# Servo8.net
KiCad netlist of a schematic drawn in EAGLE
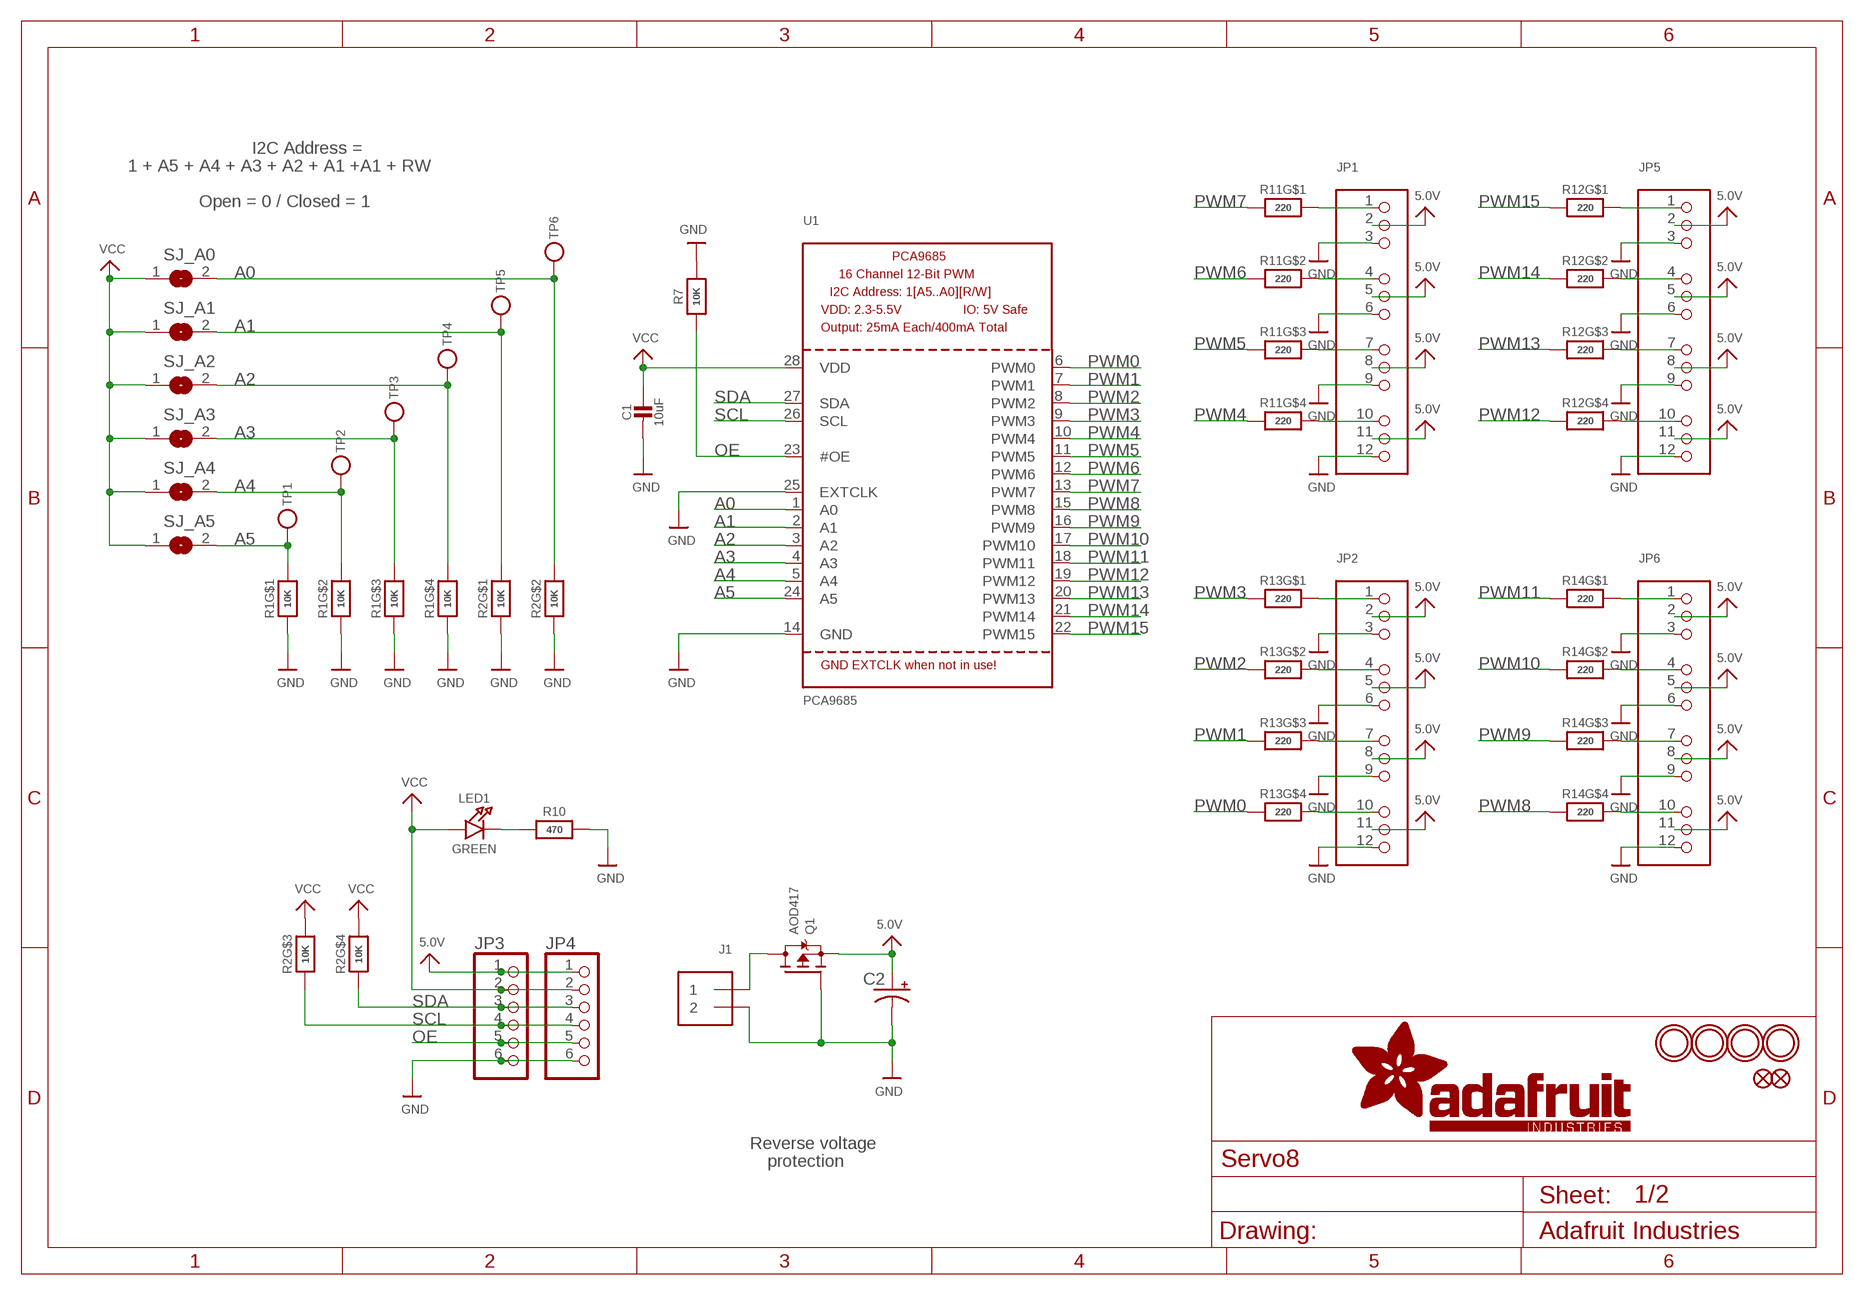
[diagram p0: schematic, sheet 1]
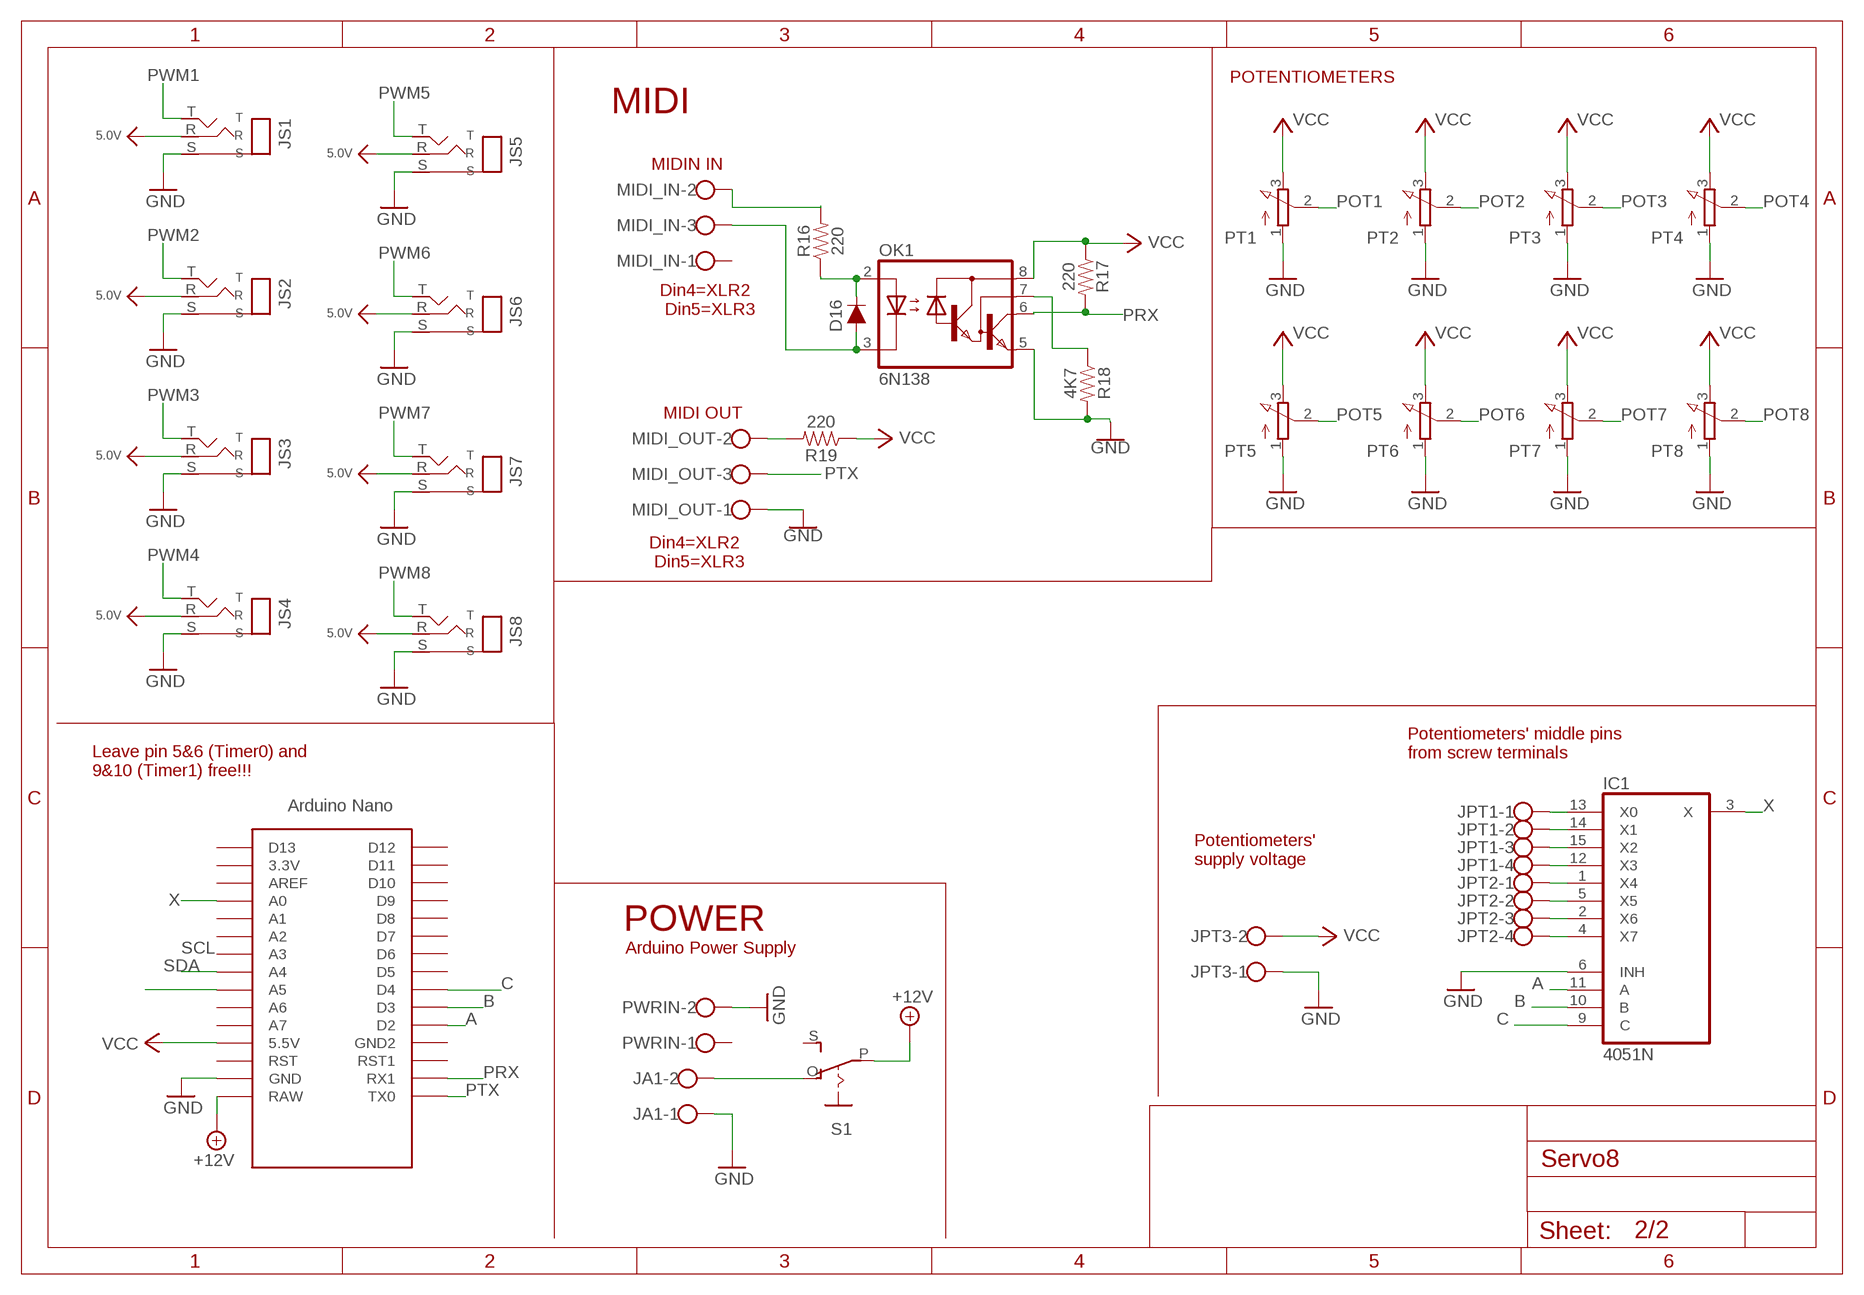
[diagram p1: schematic, sheet 2]

(export (version "E")
  (design (tool "Eeschema 10.0.6"))
  (components
    (comp (ref "C1")
      (value "10uF")
      (footprint "eagle-import:0805-NO")
      (libsource (lib "eagle-import") (part "CAP_CERAMIC0805-NOOUTLINE"))
    )
    (comp (ref "C2")
      (value "CPOL-USE3.5-8")
      (footprint "eagle-import:E3,5-8")
      (libsource (lib "eagle-import") (part "CPOL-USE3.5-8"))
    )
    (comp (ref "FID1")
      (value "FIDUCIAL\"\"")
      (footprint "eagle-import:FIDUCIAL_1MM")
      (libsource (lib "eagle-import") (part "FIDUCIAL{dblquote}{dblquote}"))
    )
    (comp (ref "FID2")
      (value "FIDUCIAL\"\"")
      (footprint "eagle-import:FIDUCIAL_1MM")
      (libsource (lib "eagle-import") (part "FIDUCIAL{dblquote}{dblquote}"))
    )
    (comp (ref "J1")
      (value "TERMBLOCK_1X2")
      (footprint "eagle-import:TERMBLOCK_1X2-3.5MM")
      (libsource (lib "eagle-import") (part "TERMBLOCK_1X2"))
    )
    (comp (ref "JP1")
      (value "HEADER-3X04")
      (footprint "eagle-import:3X04")
      (libsource (lib "eagle-import") (part "HEADER-3X04"))
    )
    (comp (ref "JP2")
      (value "HEADER-3X04")
      (footprint "eagle-import:3X04")
      (libsource (lib "eagle-import") (part "HEADER-3X04"))
    )
    (comp (ref "JP3")
      (value "PINHD-1X6CB")
      (footprint "eagle-import:1X06-CLEANBIG")
      (libsource (lib "eagle-import") (part "PINHD-1X6CB"))
    )
    (comp (ref "JP4")
      (value "PINHD-1X6CB")
      (footprint "eagle-import:1X06-CLEANBIG")
      (libsource (lib "eagle-import") (part "PINHD-1X6CB"))
    )
    (comp (ref "JP5")
      (value "HEADER-3X04")
      (footprint "eagle-import:3X04")
      (libsource (lib "eagle-import") (part "HEADER-3X04"))
    )
    (comp (ref "JP6")
      (value "HEADER-3X04")
      (footprint "eagle-import:3X04")
      (libsource (lib "eagle-import") (part "HEADER-3X04"))
    )
    (comp (ref "LED1")
      (value "GREEN")
      (footprint "eagle-import:CHIPLED_0805_NOOUTLINE")
      (libsource (lib "eagle-import") (part "LED0805_NOOUTLINE"))
    )
    (comp (ref "Q1")
      (value "AOD417")
      (footprint "eagle-import:TO252")
      (libsource (lib "eagle-import") (part "MOSFET-PTO252"))
    )
    (comp (ref "R1")
      (value "10K")
      (footprint "eagle-import:RESPACK_4X0603")
      (libsource (lib "eagle-import") (part "RESISTOR_4PACK"))
    )
    (comp (ref "R2")
      (value "10K")
      (footprint "eagle-import:RESPACK_4X0603")
      (libsource (lib "eagle-import") (part "RESISTOR_4PACK"))
    )
    (comp (ref "R7")
      (value "10K")
      (footprint "eagle-import:0805-NO")
      (libsource (lib "eagle-import") (part "RESISTOR0805_NOOUTLINE"))
    )
    (comp (ref "R10")
      (value "470")
      (footprint "eagle-import:_0805MP")
      (libsource (lib "eagle-import") (part "RESISTOR_0805MP"))
    )
    (comp (ref "R11")
      (value "220")
      (footprint "eagle-import:RESPACK_4X0603")
      (libsource (lib "eagle-import") (part "RESISTOR_4PACK"))
    )
    (comp (ref "R12")
      (value "220")
      (footprint "eagle-import:RESPACK_4X0603")
      (libsource (lib "eagle-import") (part "RESISTOR_4PACK"))
    )
    (comp (ref "R13")
      (value "220")
      (footprint "eagle-import:RESPACK_4X0603")
      (libsource (lib "eagle-import") (part "RESISTOR_4PACK"))
    )
    (comp (ref "R14")
      (value "220")
      (footprint "eagle-import:RESPACK_4X0603")
      (libsource (lib "eagle-import") (part "RESISTOR_4PACK"))
    )
    (comp (ref "SJ_A0")
      (value "SOLDERJUMPERREFLOW_NOPASTE")
      (footprint "eagle-import:SOLDERJUMPER_REFLOW_NOPASTE")
      (libsource (lib "eagle-import") (part "SOLDERJUMPERREFLOW_NOPASTE"))
    )
    (comp (ref "SJ_A1")
      (value "SOLDERJUMPERREFLOW_NOPASTE")
      (footprint "eagle-import:SOLDERJUMPER_REFLOW_NOPASTE")
      (libsource (lib "eagle-import") (part "SOLDERJUMPERREFLOW_NOPASTE"))
    )
    (comp (ref "SJ_A2")
      (value "SOLDERJUMPERREFLOW_NOPASTE")
      (footprint "eagle-import:SOLDERJUMPER_REFLOW_NOPASTE")
      (libsource (lib "eagle-import") (part "SOLDERJUMPERREFLOW_NOPASTE"))
    )
    (comp (ref "SJ_A3")
      (value "SOLDERJUMPERREFLOW_NOPASTE")
      (footprint "eagle-import:SOLDERJUMPER_REFLOW_NOPASTE")
      (libsource (lib "eagle-import") (part "SOLDERJUMPERREFLOW_NOPASTE"))
    )
    (comp (ref "SJ_A4")
      (value "SOLDERJUMPERREFLOW_NOPASTE")
      (footprint "eagle-import:SOLDERJUMPER_REFLOW_NOPASTE")
      (libsource (lib "eagle-import") (part "SOLDERJUMPERREFLOW_NOPASTE"))
    )
    (comp (ref "SJ_A5")
      (value "SOLDERJUMPERREFLOW_NOPASTE")
      (footprint "eagle-import:SOLDERJUMPER_REFLOW_NOPASTE")
      (libsource (lib "eagle-import") (part "SOLDERJUMPERREFLOW_NOPASTE"))
    )
    (comp (ref "TP1")
      (value "TESTPOINTROUND1MM")
      (footprint "eagle-import:TESTPOINT_ROUND_1MM")
      (libsource (lib "eagle-import") (part "TESTPOINTROUND1MM"))
    )
    (comp (ref "TP2")
      (value "TESTPOINTROUND1MM")
      (footprint "eagle-import:TESTPOINT_ROUND_1MM")
      (libsource (lib "eagle-import") (part "TESTPOINTROUND1MM"))
    )
    (comp (ref "TP3")
      (value "TESTPOINTROUND1MM")
      (footprint "eagle-import:TESTPOINT_ROUND_1MM")
      (libsource (lib "eagle-import") (part "TESTPOINTROUND1MM"))
    )
    (comp (ref "TP4")
      (value "TESTPOINTROUND1MM")
      (footprint "eagle-import:TESTPOINT_ROUND_1MM")
      (libsource (lib "eagle-import") (part "TESTPOINTROUND1MM"))
    )
    (comp (ref "TP5")
      (value "TESTPOINTROUND1MM")
      (footprint "eagle-import:TESTPOINT_ROUND_1MM")
      (libsource (lib "eagle-import") (part "TESTPOINTROUND1MM"))
    )
    (comp (ref "TP6")
      (value "TESTPOINTROUND1MM")
      (footprint "eagle-import:TESTPOINT_ROUND_1MM")
      (libsource (lib "eagle-import") (part "TESTPOINTROUND1MM"))
    )
    (comp (ref "U$47")
      (value "MOUNTINGHOLE2.5")
      (footprint "eagle-import:MOUNTINGHOLE_2.5_PLATED")
      (libsource (lib "eagle-import") (part "MOUNTINGHOLE2.5"))
    )
    (comp (ref "U$48")
      (value "MOUNTINGHOLE2.5")
      (footprint "eagle-import:MOUNTINGHOLE_2.5_PLATED")
      (libsource (lib "eagle-import") (part "MOUNTINGHOLE2.5"))
    )
    (comp (ref "U$49")
      (value "MOUNTINGHOLE2.5")
      (footprint "eagle-import:MOUNTINGHOLE_2.5_PLATED")
      (libsource (lib "eagle-import") (part "MOUNTINGHOLE2.5"))
    )
    (comp (ref "U$50")
      (value "MOUNTINGHOLE2.5")
      (footprint "eagle-import:MOUNTINGHOLE_2.5_PLATED")
      (libsource (lib "eagle-import") (part "MOUNTINGHOLE2.5"))
    )
    (comp (ref "U1")
      (value "PCA9685")
      (footprint "eagle-import:TSSOP28")
      (libsource (lib "eagle-import") (part "PCA9685"))
    )
    (comp (ref "D16")
      (value "200mA/100V/1V")
      (footprint "eagle-import:DIODE-1N4148")
      (libsource (lib "eagle-import") (part "DIODE-1N4148"))
    )
    (comp (ref "IC1")
      (value "4051N")
      (footprint "eagle-import:DIL16")
      (libsource (lib "eagle-import") (part "4051N"))
    )
    (comp (ref "JA1")
      (value "W237-102")
      (footprint "eagle-import:W237-102")
      (fields (field (name "MPN") "237-102"))
      (libsource (lib "eagle-import") (part "W237-102"))
    )
    (comp (ref "JPT1")
      (value "W237-4")
      (footprint "eagle-import:W237-4")
      (libsource (lib "eagle-import") (part "W237-4"))
    )
    (comp (ref "JPT2")
      (value "W237-4")
      (footprint "eagle-import:W237-4")
      (libsource (lib "eagle-import") (part "W237-4"))
    )
    (comp (ref "JPT3")
      (value "W237-102")
      (footprint "eagle-import:W237-102")
      (fields (field (name "MPN") "237-102"))
      (libsource (lib "eagle-import") (part "W237-102"))
    )
    (comp (ref "JS1")
      (value "STEREOREV")
      (footprint "eagle-import:STEREO_JACK_MIRROR")
      (libsource (lib "eagle-import") (part "STEREOREV"))
    )
    (comp (ref "JS2")
      (value "STEREOREV")
      (footprint "eagle-import:STEREO_JACK_MIRROR")
      (libsource (lib "eagle-import") (part "STEREOREV"))
    )
    (comp (ref "JS3")
      (value "STEREOREV")
      (footprint "eagle-import:STEREO_JACK_MIRROR")
      (libsource (lib "eagle-import") (part "STEREOREV"))
    )
    (comp (ref "JS4")
      (value "STEREOREV")
      (footprint "eagle-import:STEREO_JACK_MIRROR")
      (libsource (lib "eagle-import") (part "STEREOREV"))
    )
    (comp (ref "JS5")
      (value "STEREOREV")
      (footprint "eagle-import:STEREO_JACK_MIRROR")
      (libsource (lib "eagle-import") (part "STEREOREV"))
    )
    (comp (ref "JS6")
      (value "STEREOREV")
      (footprint "eagle-import:STEREO_JACK_MIRROR")
      (libsource (lib "eagle-import") (part "STEREOREV"))
    )
    (comp (ref "JS7")
      (value "STEREOREV")
      (footprint "eagle-import:STEREO_JACK_MIRROR")
      (libsource (lib "eagle-import") (part "STEREOREV"))
    )
    (comp (ref "JS8")
      (value "STEREOREV")
      (footprint "eagle-import:STEREO_JACK_MIRROR")
      (libsource (lib "eagle-import") (part "STEREOREV"))
    )
    (comp (ref "MIDI_IN")
      (value "W237-103")
      (footprint "eagle-import:W237-103")
      (fields (field (name "MPN") "237-103"))
      (libsource (lib "eagle-import") (part "W237-103"))
    )
    (comp (ref "MIDI_OUT")
      (value "W237-103")
      (footprint "eagle-import:W237-103")
      (fields (field (name "MPN") "237-103"))
      (libsource (lib "eagle-import") (part "W237-103"))
    )
    (comp (ref "OK1")
      (value "6N138")
      (footprint "eagle-import:DIL08")
      (fields (field (name "MF") "VISHAY/TELEFUNKEN"))
      (libsource (lib "eagle-import") (part "6N138"))
    )
    (comp (ref "PT1")
      (value "3RP/1610N")
      (footprint "eagle-import:3RP_1610N")
      (libsource (lib "eagle-import") (part "3RP/1610N"))
    )
    (comp (ref "PT2")
      (value "3RP/1610N")
      (footprint "eagle-import:3RP_1610N")
      (libsource (lib "eagle-import") (part "3RP/1610N"))
    )
    (comp (ref "PT3")
      (value "3RP/1610N")
      (footprint "eagle-import:3RP_1610N")
      (libsource (lib "eagle-import") (part "3RP/1610N"))
    )
    (comp (ref "PT4")
      (value "3RP/1610N")
      (footprint "eagle-import:3RP_1610N")
      (libsource (lib "eagle-import") (part "3RP/1610N"))
    )
    (comp (ref "PT5")
      (value "3RP/1610N")
      (footprint "eagle-import:3RP_1610N")
      (libsource (lib "eagle-import") (part "3RP/1610N"))
    )
    (comp (ref "PT6")
      (value "3RP/1610N")
      (footprint "eagle-import:3RP_1610N")
      (libsource (lib "eagle-import") (part "3RP/1610N"))
    )
    (comp (ref "PT7")
      (value "3RP/1610N")
      (footprint "eagle-import:3RP_1610N")
      (libsource (lib "eagle-import") (part "3RP/1610N"))
    )
    (comp (ref "PT8")
      (value "3RP/1610N")
      (footprint "eagle-import:3RP_1610N")
      (libsource (lib "eagle-import") (part "3RP/1610N"))
    )
    (comp (ref "PWRIN")
      (value "W237-4")
      (footprint "eagle-import:W237-4")
      (libsource (lib "eagle-import") (part "W237-4"))
    )
    (comp (ref "R16")
      (value "220")
      (footprint "eagle-import:AXIAL-0.3")
      (libsource (lib "eagle-import") (part "1KOHM-HORIZ-1/4W-5%"))
    )
    (comp (ref "R17")
      (value "220")
      (footprint "eagle-import:AXIAL-0.3")
      (libsource (lib "eagle-import") (part "1KOHM-HORIZ-1/4W-5%"))
    )
    (comp (ref "R18")
      (value "4K7")
      (footprint "eagle-import:AXIAL-0.3")
      (libsource (lib "eagle-import") (part "1KOHM-HORIZ-1/4W-5%"))
    )
    (comp (ref "R19")
      (value "220")
      (footprint "eagle-import:AXIAL-0.3")
      (libsource (lib "eagle-import") (part "1KOHM-HORIZ-1/4W-5%"))
    )
    (comp (ref "S1")
      (value "EG1218S")
      (footprint "eagle-import:EG1218")
      (libsource (lib "eagle-import") (part "EG1218S"))
    )
    (comp (ref "U$55")
      (value "NANO")
      (footprint "eagle-import:NANO")
      (libsource (lib "eagle-import") (part "NANO"))
    )
  )
  (nets
    (net (code "1") (name "+12V") (class "Default")
      (node (ref "S1") (pin "P") (pinfunction "P_P") (pintype "passive"))
      (node (ref "U$55") (pin "RAW") (pinfunction "RAW_RAW") (pintype "bidirectional"))
    )
    (net (code "2") (name "5.0V") (class "Default")
      (node (ref "C2") (pin "+") (pinfunction "+_+") (pintype "passive"))
      (node (ref "JP1") (pin "11") (pinfunction "11_11") (pintype "passive"))
      (node (ref "JP1") (pin "2") (pinfunction "2_2") (pintype "passive"))
      (node (ref "JP1") (pin "5") (pinfunction "5_5") (pintype "passive"))
      (node (ref "JP1") (pin "8") (pinfunction "8_8") (pintype "passive"))
      (node (ref "JP2") (pin "11") (pinfunction "11_11") (pintype "passive"))
      (node (ref "JP2") (pin "2") (pinfunction "2_2") (pintype "passive"))
      (node (ref "JP2") (pin "5") (pinfunction "5_5") (pintype "passive"))
      (node (ref "JP2") (pin "8") (pinfunction "8_8") (pintype "passive"))
      (node (ref "JP3") (pin "1") (pinfunction "1_1") (pintype "passive"))
      (node (ref "JP4") (pin "1") (pinfunction "1_1") (pintype "passive"))
      (node (ref "JP5") (pin "11") (pinfunction "11_11") (pintype "passive"))
      (node (ref "JP5") (pin "2") (pinfunction "2_2") (pintype "passive"))
      (node (ref "JP5") (pin "5") (pinfunction "5_5") (pintype "passive"))
      (node (ref "JP5") (pin "8") (pinfunction "8_8") (pintype "passive"))
      (node (ref "JP6") (pin "11") (pinfunction "11_11") (pintype "passive"))
      (node (ref "JP6") (pin "2") (pinfunction "2_2") (pintype "passive"))
      (node (ref "JP6") (pin "5") (pinfunction "5_5") (pintype "passive"))
      (node (ref "JP6") (pin "8") (pinfunction "8_8") (pintype "passive"))
      (node (ref "JS1") (pin "R") (pinfunction "R_R") (pintype "passive"))
      (node (ref "JS2") (pin "R") (pinfunction "R_R") (pintype "passive"))
      (node (ref "JS3") (pin "R") (pinfunction "R_R") (pintype "passive"))
      (node (ref "JS4") (pin "R") (pinfunction "R_R") (pintype "passive"))
      (node (ref "JS5") (pin "R") (pinfunction "R_R") (pintype "passive"))
      (node (ref "JS6") (pin "R") (pinfunction "R_R") (pintype "passive"))
      (node (ref "JS7") (pin "R") (pinfunction "R_R") (pintype "passive"))
      (node (ref "JS8") (pin "R") (pinfunction "R_R") (pintype "passive"))
      (node (ref "Q1") (pin "2") (pinfunction "S_2") (pintype "passive"))
    )
    (net (code "3") (name "A") (class "Default")
      (node (ref "IC1") (pin "11") (pinfunction "A_11") (pintype "input"))
      (node (ref "U$55") (pin "D2") (pinfunction "D2_D2") (pintype "bidirectional"))
    )
    (net (code "4") (name "A0") (class "Default")
      (node (ref "R2") (pin "7") (pinfunction "2_7") (pintype "passive"))
      (node (ref "SJ_A0") (pin "2") (pinfunction "2_2") (pintype "passive"))
      (node (ref "TP6") (pin "P$1") (pinfunction "P$1_P$1") (pintype "bidirectional"))
      (node (ref "U1") (pin "1") (pinfunction "A0_1") (pintype "bidirectional"))
    )
    (net (code "5") (name "A1") (class "Default")
      (node (ref "R2") (pin "8") (pinfunction "2_8") (pintype "passive"))
      (node (ref "SJ_A1") (pin "2") (pinfunction "2_2") (pintype "passive"))
      (node (ref "TP5") (pin "P$1") (pinfunction "P$1_P$1") (pintype "bidirectional"))
      (node (ref "U1") (pin "2") (pinfunction "A1_2") (pintype "bidirectional"))
    )
    (net (code "6") (name "A2") (class "Default")
      (node (ref "R1") (pin "5") (pinfunction "2_5") (pintype "passive"))
      (node (ref "SJ_A2") (pin "2") (pinfunction "2_2") (pintype "passive"))
      (node (ref "TP4") (pin "P$1") (pinfunction "P$1_P$1") (pintype "bidirectional"))
      (node (ref "U1") (pin "3") (pinfunction "A2_3") (pintype "bidirectional"))
    )
    (net (code "7") (name "A3") (class "Default")
      (node (ref "R1") (pin "6") (pinfunction "2_6") (pintype "passive"))
      (node (ref "SJ_A3") (pin "2") (pinfunction "2_2") (pintype "passive"))
      (node (ref "TP3") (pin "P$1") (pinfunction "P$1_P$1") (pintype "bidirectional"))
      (node (ref "U1") (pin "4") (pinfunction "A3_4") (pintype "bidirectional"))
    )
    (net (code "8") (name "A4") (class "Default")
      (node (ref "R1") (pin "7") (pinfunction "2_7") (pintype "passive"))
      (node (ref "SJ_A4") (pin "2") (pinfunction "2_2") (pintype "passive"))
      (node (ref "TP2") (pin "P$1") (pinfunction "P$1_P$1") (pintype "bidirectional"))
      (node (ref "U1") (pin "5") (pinfunction "A4_5") (pintype "bidirectional"))
    )
    (net (code "9") (name "A5") (class "Default")
      (node (ref "R1") (pin "8") (pinfunction "2_8") (pintype "passive"))
      (node (ref "SJ_A5") (pin "2") (pinfunction "2_2") (pintype "passive"))
      (node (ref "TP1") (pin "P$1") (pinfunction "P$1_P$1") (pintype "bidirectional"))
      (node (ref "U1") (pin "24") (pinfunction "A5_24") (pintype "bidirectional"))
    )
    (net (code "10") (name "B") (class "Default")
      (node (ref "IC1") (pin "10") (pinfunction "B_10") (pintype "input"))
      (node (ref "U$55") (pin "D3") (pinfunction "D3_D3") (pintype "bidirectional"))
    )
    (net (code "11") (name "C") (class "Default")
      (node (ref "IC1") (pin "9") (pinfunction "C_9") (pintype "input"))
      (node (ref "U$55") (pin "D4") (pinfunction "D4_D4") (pintype "bidirectional"))
    )
    (net (code "12") (name "GND") (class "Default")
      (node (ref "C1") (pin "2") (pinfunction "2_2") (pintype "passive"))
      (node (ref "C2") (pin "-") (pinfunction "-_-") (pintype "passive"))
      (node (ref "IC1") (pin "6") (pinfunction "INH_6") (pintype "input"))
      (node (ref "J1") (pin "2") (pinfunction "2_2") (pintype "passive"))
      (node (ref "JA1") (pin "1") (pinfunction "KL_1") (pintype "passive"))
      (node (ref "JP1") (pin "12") (pinfunction "12_12") (pintype "passive"))
      (node (ref "JP1") (pin "3") (pinfunction "3_3") (pintype "passive"))
      (node (ref "JP1") (pin "6") (pinfunction "6_6") (pintype "passive"))
      (node (ref "JP1") (pin "9") (pinfunction "9_9") (pintype "passive"))
      (node (ref "JP2") (pin "12") (pinfunction "12_12") (pintype "passive"))
      (node (ref "JP2") (pin "3") (pinfunction "3_3") (pintype "passive"))
      (node (ref "JP2") (pin "6") (pinfunction "6_6") (pintype "passive"))
      (node (ref "JP2") (pin "9") (pinfunction "9_9") (pintype "passive"))
      (node (ref "JP3") (pin "6") (pinfunction "6_6") (pintype "passive"))
      (node (ref "JP4") (pin "6") (pinfunction "6_6") (pintype "passive"))
      (node (ref "JP5") (pin "12") (pinfunction "12_12") (pintype "passive"))
      (node (ref "JP5") (pin "3") (pinfunction "3_3") (pintype "passive"))
      (node (ref "JP5") (pin "6") (pinfunction "6_6") (pintype "passive"))
      (node (ref "JP5") (pin "9") (pinfunction "9_9") (pintype "passive"))
      (node (ref "JP6") (pin "12") (pinfunction "12_12") (pintype "passive"))
      (node (ref "JP6") (pin "3") (pinfunction "3_3") (pintype "passive"))
      (node (ref "JP6") (pin "6") (pinfunction "6_6") (pintype "passive"))
      (node (ref "JP6") (pin "9") (pinfunction "9_9") (pintype "passive"))
      (node (ref "JPT3") (pin "1") (pinfunction "KL_1") (pintype "passive"))
      (node (ref "JS1") (pin "S") (pinfunction "S_S") (pintype "passive"))
      (node (ref "JS2") (pin "S") (pinfunction "S_S") (pintype "passive"))
      (node (ref "JS3") (pin "S") (pinfunction "S_S") (pintype "passive"))
      (node (ref "JS4") (pin "S") (pinfunction "S_S") (pintype "passive"))
      (node (ref "JS5") (pin "S") (pinfunction "S_S") (pintype "passive"))
      (node (ref "JS6") (pin "S") (pinfunction "S_S") (pintype "passive"))
      (node (ref "JS7") (pin "S") (pinfunction "S_S") (pintype "passive"))
      (node (ref "JS8") (pin "S") (pinfunction "S_S") (pintype "passive"))
      (node (ref "MIDI_OUT") (pin "1") (pinfunction "KL_1") (pintype "passive"))
      (node (ref "OK1") (pin "5") (pinfunction "GND_5") (pintype "passive"))
      (node (ref "PT1") (pin "1") (pinfunction "A_1") (pintype "passive"))
      (node (ref "PT2") (pin "1") (pinfunction "A_1") (pintype "passive"))
      (node (ref "PT3") (pin "1") (pinfunction "A_1") (pintype "passive"))
      (node (ref "PT4") (pin "1") (pinfunction "A_1") (pintype "passive"))
      (node (ref "PT5") (pin "1") (pinfunction "A_1") (pintype "passive"))
      (node (ref "PT6") (pin "1") (pinfunction "A_1") (pintype "passive"))
      (node (ref "PT7") (pin "1") (pinfunction "A_1") (pintype "passive"))
      (node (ref "PT8") (pin "1") (pinfunction "A_1") (pintype "passive"))
      (node (ref "PWRIN") (pin "2") (pinfunction "KL_2") (pintype "passive"))
      (node (ref "Q1") (pin "1") (pinfunction "G_1") (pintype "passive"))
      (node (ref "R1") (pin "1") (pinfunction "1_1") (pintype "passive"))
      (node (ref "R1") (pin "2") (pinfunction "1_2") (pintype "passive"))
      (node (ref "R1") (pin "3") (pinfunction "1_3") (pintype "passive"))
      (node (ref "R1") (pin "4") (pinfunction "1_4") (pintype "passive"))
      (node (ref "R10") (pin "2") (pinfunction "2_2") (pintype "passive"))
      (node (ref "R18") (pin "P$2") (pinfunction "2_P$2") (pintype "passive"))
      (node (ref "R2") (pin "1") (pinfunction "1_1") (pintype "passive"))
      (node (ref "R2") (pin "2") (pinfunction "1_2") (pintype "passive"))
      (node (ref "R7") (pin "2") (pinfunction "2_2") (pintype "passive"))
      (node (ref "U$55") (pin "GND") (pinfunction "GND_GND") (pintype "bidirectional"))
      (node (ref "U1") (pin "14") (pinfunction "GND_14") (pintype "power_in"))
      (node (ref "U1") (pin "25") (pinfunction "EXTCLK_25") (pintype "input"))
    )
    (net (code "13") (name "Net-(JA1B-KL)") (class "Default")
      (node (ref "JA1") (pin "2") (pinfunction "KL_2") (pintype "passive"))
      (node (ref "S1") (pin "O") (pinfunction "O_O") (pintype "passive"))
    )
    (net (code "14") (name "Net-(LED1-PadC)") (class "Default")
      (node (ref "LED1") (pin "C") (pinfunction "C_C") (pintype "passive"))
      (node (ref "R10") (pin "1") (pinfunction "1_1") (pintype "passive"))
    )
    (net (code "15") (name "Net-(MIDI_INB-KL)") (class "Default")
      (node (ref "MIDI_IN") (pin "2") (pinfunction "KL_2") (pintype "passive"))
      (node (ref "R16") (pin "P$2") (pinfunction "2_P$2") (pintype "passive"))
    )
    (net (code "16") (name "Net-(MIDI_INC-KL)") (class "Default")
      (node (ref "D16") (pin "A") (pinfunction "A_A") (pintype "passive"))
      (node (ref "MIDI_IN") (pin "3") (pinfunction "KL_3") (pintype "passive"))
      (node (ref "OK1") (pin "3") (pinfunction "C_3") (pintype "passive"))
    )
    (net (code "17") (name "Net-(MIDI_OUTB-KL)") (class "Default")
      (node (ref "MIDI_OUT") (pin "2") (pinfunction "KL_2") (pintype "passive"))
      (node (ref "R19") (pin "P$2") (pinfunction "2_P$2") (pintype "passive"))
    )
    (net (code "18") (name "Net-(OK1-A)") (class "Default")
      (node (ref "D16") (pin "C") (pinfunction "C_C") (pintype "passive"))
      (node (ref "OK1") (pin "2") (pinfunction "A_2") (pintype "passive"))
      (node (ref "R16") (pin "P$1") (pinfunction "1_P$1") (pintype "passive"))
    )
    (net (code "19") (name "Net-(OK1-VB)") (class "Default")
      (node (ref "OK1") (pin "7") (pinfunction "VB_7") (pintype "passive"))
      (node (ref "R18") (pin "P$1") (pinfunction "1_P$1") (pintype "passive"))
    )
    (net (code "20") (name "Net-(Q1-D)") (class "Default")
      (node (ref "J1") (pin "1") (pinfunction "1_1") (pintype "passive"))
      (node (ref "Q1") (pin "3") (pinfunction "D_3") (pintype "passive"))
    )
    (net (code "21") (name "Net-(R11A-2)") (class "Default")
      (node (ref "JP1") (pin "1") (pinfunction "1_1") (pintype "passive"))
      (node (ref "R11") (pin "8") (pinfunction "2_8") (pintype "passive"))
    )
    (net (code "22") (name "Net-(R11B-2)") (class "Default")
      (node (ref "JP1") (pin "4") (pinfunction "4_4") (pintype "passive"))
      (node (ref "R11") (pin "7") (pinfunction "2_7") (pintype "passive"))
    )
    (net (code "23") (name "Net-(R11C-2)") (class "Default")
      (node (ref "JP1") (pin "7") (pinfunction "7_7") (pintype "passive"))
      (node (ref "R11") (pin "6") (pinfunction "2_6") (pintype "passive"))
    )
    (net (code "24") (name "Net-(R11D-2)") (class "Default")
      (node (ref "JP1") (pin "10") (pinfunction "10_10") (pintype "passive"))
      (node (ref "R11") (pin "5") (pinfunction "2_5") (pintype "passive"))
    )
    (net (code "25") (name "Net-(R12A-2)") (class "Default")
      (node (ref "JP5") (pin "1") (pinfunction "1_1") (pintype "passive"))
      (node (ref "R12") (pin "8") (pinfunction "2_8") (pintype "passive"))
    )
    (net (code "26") (name "Net-(R12B-2)") (class "Default")
      (node (ref "JP5") (pin "4") (pinfunction "4_4") (pintype "passive"))
      (node (ref "R12") (pin "7") (pinfunction "2_7") (pintype "passive"))
    )
    (net (code "27") (name "Net-(R12C-2)") (class "Default")
      (node (ref "JP5") (pin "7") (pinfunction "7_7") (pintype "passive"))
      (node (ref "R12") (pin "6") (pinfunction "2_6") (pintype "passive"))
    )
    (net (code "28") (name "Net-(R12D-2)") (class "Default")
      (node (ref "JP5") (pin "10") (pinfunction "10_10") (pintype "passive"))
      (node (ref "R12") (pin "5") (pinfunction "2_5") (pintype "passive"))
    )
    (net (code "29") (name "Net-(R13A-2)") (class "Default")
      (node (ref "JP2") (pin "1") (pinfunction "1_1") (pintype "passive"))
      (node (ref "R13") (pin "8") (pinfunction "2_8") (pintype "passive"))
    )
    (net (code "30") (name "Net-(R13B-2)") (class "Default")
      (node (ref "JP2") (pin "4") (pinfunction "4_4") (pintype "passive"))
      (node (ref "R13") (pin "7") (pinfunction "2_7") (pintype "passive"))
    )
    (net (code "31") (name "Net-(R13C-2)") (class "Default")
      (node (ref "JP2") (pin "7") (pinfunction "7_7") (pintype "passive"))
      (node (ref "R13") (pin "6") (pinfunction "2_6") (pintype "passive"))
    )
    (net (code "32") (name "Net-(R13D-2)") (class "Default")
      (node (ref "JP2") (pin "10") (pinfunction "10_10") (pintype "passive"))
      (node (ref "R13") (pin "5") (pinfunction "2_5") (pintype "passive"))
    )
    (net (code "33") (name "Net-(R14A-2)") (class "Default")
      (node (ref "JP6") (pin "1") (pinfunction "1_1") (pintype "passive"))
      (node (ref "R14") (pin "8") (pinfunction "2_8") (pintype "passive"))
    )
    (net (code "34") (name "Net-(R14B-2)") (class "Default")
      (node (ref "JP6") (pin "4") (pinfunction "4_4") (pintype "passive"))
      (node (ref "R14") (pin "7") (pinfunction "2_7") (pintype "passive"))
    )
    (net (code "35") (name "Net-(R14C-2)") (class "Default")
      (node (ref "JP6") (pin "7") (pinfunction "7_7") (pintype "passive"))
      (node (ref "R14") (pin "6") (pinfunction "2_6") (pintype "passive"))
    )
    (net (code "36") (name "Net-(R14D-2)") (class "Default")
      (node (ref "JP6") (pin "10") (pinfunction "10_10") (pintype "passive"))
      (node (ref "R14") (pin "5") (pinfunction "2_5") (pintype "passive"))
    )
    (net (code "37") (name "OE") (class "Default")
      (node (ref "JP3") (pin "5") (pinfunction "5_5") (pintype "passive"))
      (node (ref "JP4") (pin "5") (pinfunction "5_5") (pintype "passive"))
      (node (ref "R7") (pin "1") (pinfunction "1_1") (pintype "passive"))
      (node (ref "U1") (pin "23") (pinfunction "#OE_23") (pintype "input"))
    )
    (net (code "38") (name "POT1") (class "Default")
      (node (ref "IC1") (pin "13") (pinfunction "X0_13") (pintype "bidirectional"))
      (node (ref "JPT1") (pin "1") (pinfunction "KL_1") (pintype "passive"))
      (node (ref "PT1") (pin "2") (pinfunction "S_2") (pintype "passive"))
    )
    (net (code "39") (name "POT2") (class "Default")
      (node (ref "IC1") (pin "14") (pinfunction "X1_14") (pintype "bidirectional"))
      (node (ref "JPT1") (pin "2") (pinfunction "KL_2") (pintype "passive"))
      (node (ref "PT2") (pin "2") (pinfunction "S_2") (pintype "passive"))
    )
    (net (code "40") (name "POT3") (class "Default")
      (node (ref "IC1") (pin "15") (pinfunction "X2_15") (pintype "bidirectional"))
      (node (ref "JPT1") (pin "3") (pinfunction "KL_3") (pintype "passive"))
      (node (ref "PT3") (pin "2") (pinfunction "S_2") (pintype "passive"))
    )
    (net (code "41") (name "POT4") (class "Default")
      (node (ref "IC1") (pin "12") (pinfunction "X3_12") (pintype "bidirectional"))
      (node (ref "JPT1") (pin "4") (pinfunction "KL_4") (pintype "passive"))
      (node (ref "PT4") (pin "2") (pinfunction "S_2") (pintype "passive"))
    )
    (net (code "42") (name "POT5") (class "Default")
      (node (ref "IC1") (pin "1") (pinfunction "X4_1") (pintype "bidirectional"))
      (node (ref "JPT2") (pin "1") (pinfunction "KL_1") (pintype "passive"))
      (node (ref "PT5") (pin "2") (pinfunction "S_2") (pintype "passive"))
    )
    (net (code "43") (name "POT6") (class "Default")
      (node (ref "IC1") (pin "5") (pinfunction "X5_5") (pintype "bidirectional"))
      (node (ref "JPT2") (pin "2") (pinfunction "KL_2") (pintype "passive"))
      (node (ref "PT6") (pin "2") (pinfunction "S_2") (pintype "passive"))
    )
    (net (code "44") (name "POT7") (class "Default")
      (node (ref "IC1") (pin "2") (pinfunction "X6_2") (pintype "bidirectional"))
      (node (ref "JPT2") (pin "3") (pinfunction "KL_3") (pintype "passive"))
      (node (ref "PT7") (pin "2") (pinfunction "S_2") (pintype "passive"))
    )
    (net (code "45") (name "POT8") (class "Default")
      (node (ref "IC1") (pin "4") (pinfunction "X7_4") (pintype "bidirectional"))
      (node (ref "JPT2") (pin "4") (pinfunction "KL_4") (pintype "passive"))
      (node (ref "PT8") (pin "2") (pinfunction "S_2") (pintype "passive"))
    )
    (net (code "46") (name "PRX") (class "Default")
      (node (ref "OK1") (pin "6") (pinfunction "VO_6") (pintype "passive"))
      (node (ref "R17") (pin "P$2") (pinfunction "2_P$2") (pintype "passive"))
      (node (ref "U$55") (pin "RX1") (pinfunction "RX1_RX1") (pintype "bidirectional"))
    )
    (net (code "47") (name "PTX") (class "Default")
      (node (ref "MIDI_OUT") (pin "3") (pinfunction "KL_3") (pintype "passive"))
      (node (ref "U$55") (pin "TX0") (pinfunction "TX0_TX0") (pintype "bidirectional"))
    )
    (net (code "48") (name "PWM0") (class "Default")
      (node (ref "R13") (pin "4") (pinfunction "1_4") (pintype "passive"))
      (node (ref "U1") (pin "6") (pinfunction "PWM0_6") (pintype "output"))
    )
    (net (code "49") (name "PWM1") (class "Default")
      (node (ref "JS1") (pin "T") (pinfunction "T_T") (pintype "passive"))
      (node (ref "R13") (pin "3") (pinfunction "1_3") (pintype "passive"))
      (node (ref "U1") (pin "7") (pinfunction "PWM1_7") (pintype "output"))
    )
    (net (code "50") (name "PWM2") (class "Default")
      (node (ref "JS2") (pin "T") (pinfunction "T_T") (pintype "passive"))
      (node (ref "R13") (pin "2") (pinfunction "1_2") (pintype "passive"))
      (node (ref "U1") (pin "8") (pinfunction "PWM2_8") (pintype "output"))
    )
    (net (code "51") (name "PWM3") (class "Default")
      (node (ref "JS3") (pin "T") (pinfunction "T_T") (pintype "passive"))
      (node (ref "R13") (pin "1") (pinfunction "1_1") (pintype "passive"))
      (node (ref "U1") (pin "9") (pinfunction "PWM3_9") (pintype "output"))
    )
    (net (code "52") (name "PWM4") (class "Default")
      (node (ref "JS4") (pin "T") (pinfunction "T_T") (pintype "passive"))
      (node (ref "R11") (pin "4") (pinfunction "1_4") (pintype "passive"))
      (node (ref "U1") (pin "10") (pinfunction "PWM4_10") (pintype "output"))
    )
    (net (code "53") (name "PWM5") (class "Default")
      (node (ref "JS5") (pin "T") (pinfunction "T_T") (pintype "passive"))
      (node (ref "R11") (pin "3") (pinfunction "1_3") (pintype "passive"))
      (node (ref "U1") (pin "11") (pinfunction "PWM5_11") (pintype "output"))
    )
    (net (code "54") (name "PWM6") (class "Default")
      (node (ref "JS6") (pin "T") (pinfunction "T_T") (pintype "passive"))
      (node (ref "R11") (pin "2") (pinfunction "1_2") (pintype "passive"))
      (node (ref "U1") (pin "12") (pinfunction "PWM6_12") (pintype "output"))
    )
    (net (code "55") (name "PWM7") (class "Default")
      (node (ref "JS7") (pin "T") (pinfunction "T_T") (pintype "passive"))
      (node (ref "R11") (pin "1") (pinfunction "1_1") (pintype "passive"))
      (node (ref "U1") (pin "13") (pinfunction "PWM7_13") (pintype "output"))
    )
    (net (code "56") (name "PWM8") (class "Default")
      (node (ref "JS8") (pin "T") (pinfunction "T_T") (pintype "passive"))
      (node (ref "R14") (pin "4") (pinfunction "1_4") (pintype "passive"))
      (node (ref "U1") (pin "15") (pinfunction "PWM8_15") (pintype "output"))
    )
    (net (code "57") (name "PWM9") (class "Default")
      (node (ref "R14") (pin "3") (pinfunction "1_3") (pintype "passive"))
      (node (ref "U1") (pin "16") (pinfunction "PWM9_16") (pintype "output"))
    )
    (net (code "58") (name "PWM10") (class "Default")
      (node (ref "R14") (pin "2") (pinfunction "1_2") (pintype "passive"))
      (node (ref "U1") (pin "17") (pinfunction "PWM10_17") (pintype "output"))
    )
    (net (code "59") (name "PWM11") (class "Default")
      (node (ref "R14") (pin "1") (pinfunction "1_1") (pintype "passive"))
      (node (ref "U1") (pin "18") (pinfunction "PWM11_18") (pintype "output"))
    )
    (net (code "60") (name "PWM12") (class "Default")
      (node (ref "R12") (pin "4") (pinfunction "1_4") (pintype "passive"))
      (node (ref "U1") (pin "19") (pinfunction "PWM12_19") (pintype "output"))
    )
    (net (code "61") (name "PWM13") (class "Default")
      (node (ref "R12") (pin "3") (pinfunction "1_3") (pintype "passive"))
      (node (ref "U1") (pin "20") (pinfunction "PWM13_20") (pintype "output"))
    )
    (net (code "62") (name "PWM14") (class "Default")
      (node (ref "R12") (pin "2") (pinfunction "1_2") (pintype "passive"))
      (node (ref "U1") (pin "21") (pinfunction "PWM14_21") (pintype "output"))
    )
    (net (code "63") (name "PWM15") (class "Default")
      (node (ref "R12") (pin "1") (pinfunction "1_1") (pintype "passive"))
      (node (ref "U1") (pin "22") (pinfunction "PWM15_22") (pintype "output"))
    )
    (net (code "64") (name "SCL") (class "Default")
      (node (ref "JP3") (pin "4") (pinfunction "4_4") (pintype "passive"))
      (node (ref "JP4") (pin "4") (pinfunction "4_4") (pintype "passive"))
      (node (ref "R2") (pin "3") (pinfunction "1_3") (pintype "passive"))
      (node (ref "U$55") (pin "A5") (pinfunction "A5_A5") (pintype "bidirectional"))
      (node (ref "U1") (pin "26") (pinfunction "SCL_26") (pintype "bidirectional"))
    )
    (net (code "65") (name "SDA") (class "Default")
      (node (ref "JP3") (pin "3") (pinfunction "3_3") (pintype "passive"))
      (node (ref "JP4") (pin "3") (pinfunction "3_3") (pintype "passive"))
      (node (ref "R2") (pin "4") (pinfunction "1_4") (pintype "passive"))
      (node (ref "U$55") (pin "A4") (pinfunction "A4_A4") (pintype "bidirectional"))
      (node (ref "U1") (pin "27") (pinfunction "SDA_27") (pintype "bidirectional"))
    )
    (net (code "66") (name "VCC") (class "Default")
      (node (ref "C1") (pin "1") (pinfunction "1_1") (pintype "passive"))
      (node (ref "JP3") (pin "2") (pinfunction "2_2") (pintype "passive"))
      (node (ref "JP4") (pin "2") (pinfunction "2_2") (pintype "passive"))
      (node (ref "JPT3") (pin "2") (pinfunction "KL_2") (pintype "passive"))
      (node (ref "LED1") (pin "A") (pinfunction "A_A") (pintype "passive"))
      (node (ref "OK1") (pin "8") (pinfunction "VCC_8") (pintype "passive"))
      (node (ref "PT1") (pin "3") (pinfunction "E_3") (pintype "passive"))
      (node (ref "PT2") (pin "3") (pinfunction "E_3") (pintype "passive"))
      (node (ref "PT3") (pin "3") (pinfunction "E_3") (pintype "passive"))
      (node (ref "PT4") (pin "3") (pinfunction "E_3") (pintype "passive"))
      (node (ref "PT5") (pin "3") (pinfunction "E_3") (pintype "passive"))
      (node (ref "PT6") (pin "3") (pinfunction "E_3") (pintype "passive"))
      (node (ref "PT7") (pin "3") (pinfunction "E_3") (pintype "passive"))
      (node (ref "PT8") (pin "3") (pinfunction "E_3") (pintype "passive"))
      (node (ref "R17") (pin "P$1") (pinfunction "1_P$1") (pintype "passive"))
      (node (ref "R19") (pin "P$1") (pinfunction "1_P$1") (pintype "passive"))
      (node (ref "R2") (pin "5") (pinfunction "2_5") (pintype "passive"))
      (node (ref "R2") (pin "6") (pinfunction "2_6") (pintype "passive"))
      (node (ref "SJ_A0") (pin "1") (pinfunction "1_1") (pintype "passive"))
      (node (ref "SJ_A1") (pin "1") (pinfunction "1_1") (pintype "passive"))
      (node (ref "SJ_A2") (pin "1") (pinfunction "1_1") (pintype "passive"))
      (node (ref "SJ_A3") (pin "1") (pinfunction "1_1") (pintype "passive"))
      (node (ref "SJ_A4") (pin "1") (pinfunction "1_1") (pintype "passive"))
      (node (ref "SJ_A5") (pin "1") (pinfunction "1_1") (pintype "passive"))
      (node (ref "U$55") (pin "5V") (pinfunction "5.5V_5V") (pintype "bidirectional"))
      (node (ref "U1") (pin "28") (pinfunction "VDD_28") (pintype "power_in"))
    )
    (net (code "67") (name "X") (class "Default")
      (node (ref "IC1") (pin "3") (pinfunction "X_3") (pintype "bidirectional"))
      (node (ref "U$55") (pin "A0") (pinfunction "A0_A0") (pintype "bidirectional"))
    )
    (net (code "68") (name "unconnected-(MIDI_INA-KL-Pad1)") (class "Default")
      (node (ref "MIDI_IN") (pin "1") (pinfunction "KL_1") (pintype "passive"))
    )
    (net (code "69") (name "unconnected-(PWRINA-KL-Pad1)") (class "Default")
      (node (ref "PWRIN") (pin "1") (pinfunction "KL_1") (pintype "passive"))
    )
    (net (code "70") (name "unconnected-(S1-PadS)") (class "Default")
      (node (ref "S1") (pin "S") (pinfunction "S_S") (pintype "passive"))
    )
    (net (code "71") (name "unconnected-(U$55-GND2-PadGND1)") (class "Default")
      (node (ref "U$55") (pin "GND1") (pinfunction "GND2_GND1") (pintype "bidirectional"))
    )
    (net (code "72") (name "unconnected-(U$55-Pad3.3V)") (class "Default")
      (node (ref "U$55") (pin "3.3V") (pinfunction "3.3V_3.3V") (pintype "bidirectional"))
    )
    (net (code "73") (name "unconnected-(U$55-PadA1)") (class "Default")
      (node (ref "U$55") (pin "A1") (pinfunction "A1_A1") (pintype "bidirectional"))
    )
    (net (code "74") (name "unconnected-(U$55-PadA2)") (class "Default")
      (node (ref "U$55") (pin "A2") (pinfunction "A2_A2") (pintype "bidirectional"))
    )
    (net (code "75") (name "unconnected-(U$55-PadA3)") (class "Default")
      (node (ref "U$55") (pin "A3") (pinfunction "A3_A3") (pintype "bidirectional"))
    )
    (net (code "76") (name "unconnected-(U$55-PadA6)") (class "Default")
      (node (ref "U$55") (pin "A6") (pinfunction "A6_A6") (pintype "bidirectional"))
    )
    (net (code "77") (name "unconnected-(U$55-PadA7)") (class "Default")
      (node (ref "U$55") (pin "A7") (pinfunction "A7_A7") (pintype "bidirectional"))
    )
    (net (code "78") (name "unconnected-(U$55-PadAREF)") (class "Default")
      (node (ref "U$55") (pin "AREF") (pinfunction "AREF_AREF") (pintype "bidirectional"))
    )
    (net (code "79") (name "unconnected-(U$55-PadD5)") (class "Default")
      (node (ref "U$55") (pin "D5") (pinfunction "D5_D5") (pintype "bidirectional"))
    )
    (net (code "80") (name "unconnected-(U$55-PadD6)") (class "Default")
      (node (ref "U$55") (pin "D6") (pinfunction "D6_D6") (pintype "bidirectional"))
    )
    (net (code "81") (name "unconnected-(U$55-PadD7)") (class "Default")
      (node (ref "U$55") (pin "D7") (pinfunction "D7_D7") (pintype "bidirectional"))
    )
    (net (code "82") (name "unconnected-(U$55-PadD8)") (class "Default")
      (node (ref "U$55") (pin "D8") (pinfunction "D8_D8") (pintype "bidirectional"))
    )
    (net (code "83") (name "unconnected-(U$55-PadD9)") (class "Default")
      (node (ref "U$55") (pin "D9") (pinfunction "D9_D9") (pintype "bidirectional"))
    )
    (net (code "84") (name "unconnected-(U$55-PadD10)") (class "Default")
      (node (ref "U$55") (pin "D10") (pinfunction "D10_D10") (pintype "bidirectional"))
    )
    (net (code "85") (name "unconnected-(U$55-PadD11)") (class "Default")
      (node (ref "U$55") (pin "D11") (pinfunction "D11_D11") (pintype "bidirectional"))
    )
    (net (code "86") (name "unconnected-(U$55-PadD12)") (class "Default")
      (node (ref "U$55") (pin "D12") (pinfunction "D12_D12") (pintype "bidirectional"))
    )
    (net (code "87") (name "unconnected-(U$55-PadD13)") (class "Default")
      (node (ref "U$55") (pin "D13") (pinfunction "D13_D13") (pintype "bidirectional"))
    )
    (net (code "88") (name "unconnected-(U$55-PadICSP1)") (class "Default")
      (node (ref "U$55") (pin "ICSP1") (pinfunction "ICSP1_ICSP1") (pintype "bidirectional"))
    )
    (net (code "89") (name "unconnected-(U$55-PadICSP2)") (class "Default")
      (node (ref "U$55") (pin "ICSP2") (pinfunction "ICSP2_ICSP2") (pintype "bidirectional"))
    )
    (net (code "90") (name "unconnected-(U$55-PadICSP3)") (class "Default")
      (node (ref "U$55") (pin "ICSP3") (pinfunction "ICSP3_ICSP3") (pintype "bidirectional"))
    )
    (net (code "91") (name "unconnected-(U$55-PadICSP4)") (class "Default")
      (node (ref "U$55") (pin "ICSP4") (pinfunction "ICSP4_ICSP4") (pintype "bidirectional"))
    )
    (net (code "92") (name "unconnected-(U$55-PadICSP5)") (class "Default")
      (node (ref "U$55") (pin "ICSP5") (pinfunction "ICSP5_ICSP5") (pintype "bidirectional"))
    )
    (net (code "93") (name "unconnected-(U$55-PadICSP6)") (class "Default")
      (node (ref "U$55") (pin "ICSP6") (pinfunction "ICSP6_ICSP6") (pintype "bidirectional"))
    )
    (net (code "94") (name "unconnected-(U$55-PadRST)") (class "Default")
      (node (ref "U$55") (pin "RST") (pinfunction "RST_RST") (pintype "bidirectional"))
    )
    (net (code "95") (name "unconnected-(U$55-PadRST1)") (class "Default")
      (node (ref "U$55") (pin "RST1") (pinfunction "RST1_RST1") (pintype "bidirectional"))
    )
  )
)
